# PowCarbinBoard_General.net
KiCad netlist of a schematic drawn in Altium Designer
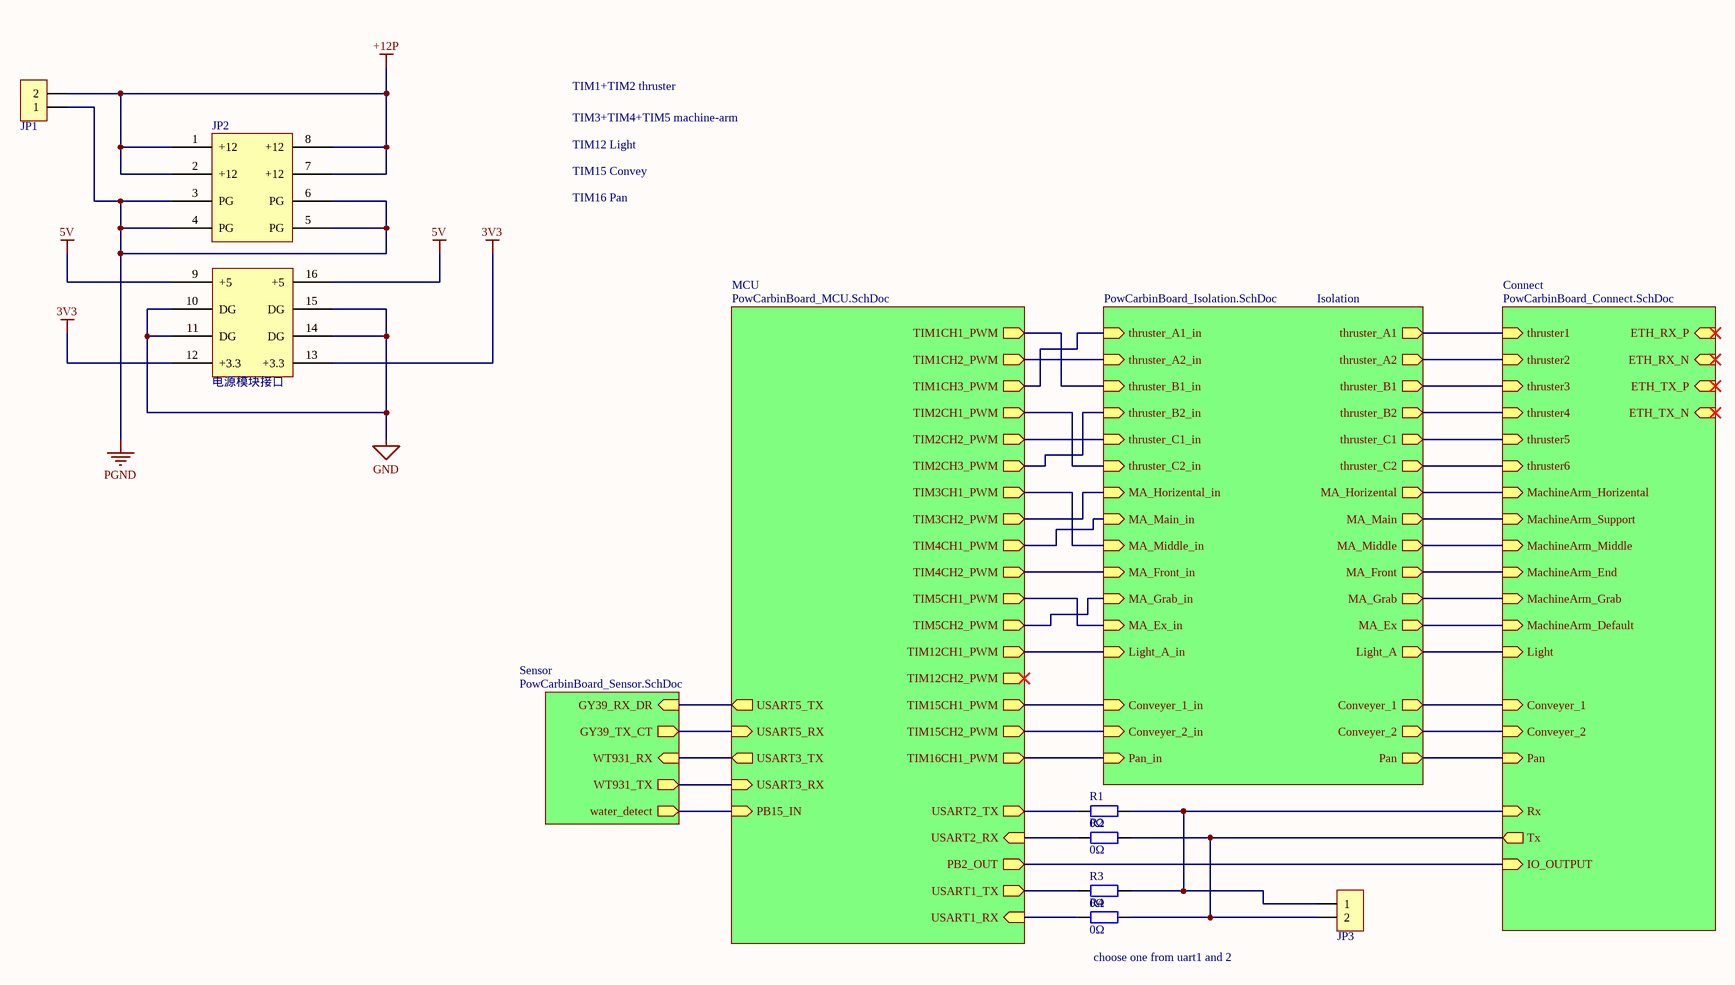
[diagram p0: PowCarbinBoard_General.SchDoc]

(export (version "E")
  (design (tool "Eeschema 10.0.6"))
  (components
    (comp (ref "JP1")
      (value "HDR-1X2")
      (footprint "KF128-5.08-2P")
      (description "2P接插件")
      (fields (field (name "版权归属") "源创客"))
      (libsource (lib "4.10 - 接插件-脚距5.08") (part "Header 2"))
    )
    (comp (ref "JP2") (value "电源模块接口") (footprint "排针-座 2*4") (libsource (lib "MySchLib") (part "电源模块接口")))
    (comp (ref "JP3")
      (value "HDR-1X2")
      (footprint "HDR2.54-LI-2P")
      (description "2P接插件")
      (fields (field (name "版权归属") "源创客"))
      (libsource (lib "4.5   - 接插件-脚距2.54") (part "Header 2"))
    )
    (comp (ref "R1")
      (value "0Ω")
      (footprint "R 0603_L")
      (description "贴片电阻")
      (fields (field (name "版权归属") "源创客"))
      (libsource (lib "3.1   - 电阻-电容-电感") (part "R"))
    )
    (comp (ref "R2")
      (value "0Ω")
      (footprint "R 0603_L")
      (description "贴片电阻")
      (fields (field (name "版权归属") "源创客"))
      (libsource (lib "3.1   - 电阻-电容-电感") (part "R"))
    )
    (comp (ref "R3")
      (value "0Ω")
      (footprint "R 0603_L")
      (description "贴片电阻")
      (fields (field (name "版权归属") "源创客"))
      (libsource (lib "3.1   - 电阻-电容-电感") (part "R"))
    )
    (comp (ref "R4")
      (value "0Ω")
      (footprint "R 0603_L")
      (description "贴片电阻")
      (fields (field (name "版权归属") "源创客"))
      (libsource (lib "3.1   - 电阻-电容-电感") (part "R"))
    )
  )
  (nets
    (net (code "1") (name "+12P") (class "Default")
      (node (ref "JP1") (pin "2") (pinfunction "2_2") (pintype "passive"))
      (node (ref "JP2") (pin "1") (pinfunction "+12_1") (pintype "passive"))
      (node (ref "JP2") (pin "2") (pinfunction "+12_2") (pintype "passive"))
      (node (ref "JP2") (pin "7") (pinfunction "+12_7") (pintype "passive"))
      (node (ref "JP2") (pin "8") (pinfunction "+12_8") (pintype "passive"))
    )
    (net (code "18") (name "/Rx") (class "Default")
      (node (ref "JP3") (pin "1") (pinfunction "1_1") (pintype "passive"))
      (node (ref "R1") (pin "2") (pinfunction "2_2") (pintype "passive"))
      (node (ref "R3") (pin "2") (pinfunction "2_2") (pintype "passive"))
    )
    (net (code "36") (name "/Tx") (class "Default")
      (node (ref "JP3") (pin "2") (pinfunction "2_2") (pintype "passive"))
      (node (ref "R2") (pin "2") (pinfunction "2_2") (pintype "passive"))
      (node (ref "R4") (pin "2") (pinfunction "2_2") (pintype "passive"))
    )
    (net (code "37") (name "/USART1_RX") (class "Default")
      (node (ref "R4") (pin "1") (pinfunction "1_1") (pintype "passive"))
    )
    (net (code "38") (name "/USART1_TX") (class "Default")
      (node (ref "R3") (pin "1") (pinfunction "1_1") (pintype "passive"))
    )
    (net (code "39") (name "/USART2_RX") (class "Default")
      (node (ref "R2") (pin "1") (pinfunction "1_1") (pintype "passive"))
    )
    (net (code "40") (name "/USART2_TX") (class "Default")
      (node (ref "R1") (pin "1") (pinfunction "1_1") (pintype "passive"))
    )
    (net (code "51") (name "3V3") (class "Default")
      (node (ref "JP2") (pin "12") (pinfunction "+3.3_12") (pintype "passive"))
      (node (ref "JP2") (pin "13") (pinfunction "+3.3_13") (pintype "passive"))
    )
    (net (code "52") (name "5V") (class "Default")
      (node (ref "JP2") (pin "16") (pinfunction "+5_16") (pintype "passive"))
      (node (ref "JP2") (pin "9") (pinfunction "+5_9") (pintype "passive"))
    )
    (net (code "53") (name "GND") (class "Default")
      (node (ref "JP2") (pin "10") (pinfunction "DG_10") (pintype "passive"))
      (node (ref "JP2") (pin "11") (pinfunction "DG_11") (pintype "passive"))
      (node (ref "JP2") (pin "14") (pinfunction "DG_14") (pintype "passive"))
      (node (ref "JP2") (pin "15") (pinfunction "DG_15") (pintype "passive"))
    )
    (net (code "54") (name "PGND") (class "Default")
      (node (ref "JP1") (pin "1") (pinfunction "1_1") (pintype "passive"))
      (node (ref "JP2") (pin "3") (pinfunction "PG_3") (pintype "passive"))
      (node (ref "JP2") (pin "4") (pinfunction "PG_4") (pintype "passive"))
      (node (ref "JP2") (pin "5") (pinfunction "PG_5") (pintype "passive"))
      (node (ref "JP2") (pin "6") (pinfunction "PG_6") (pintype "passive"))
    )
  )
)
